# bad_style.net
KiCad netlist of a schematic drawn in EAGLE
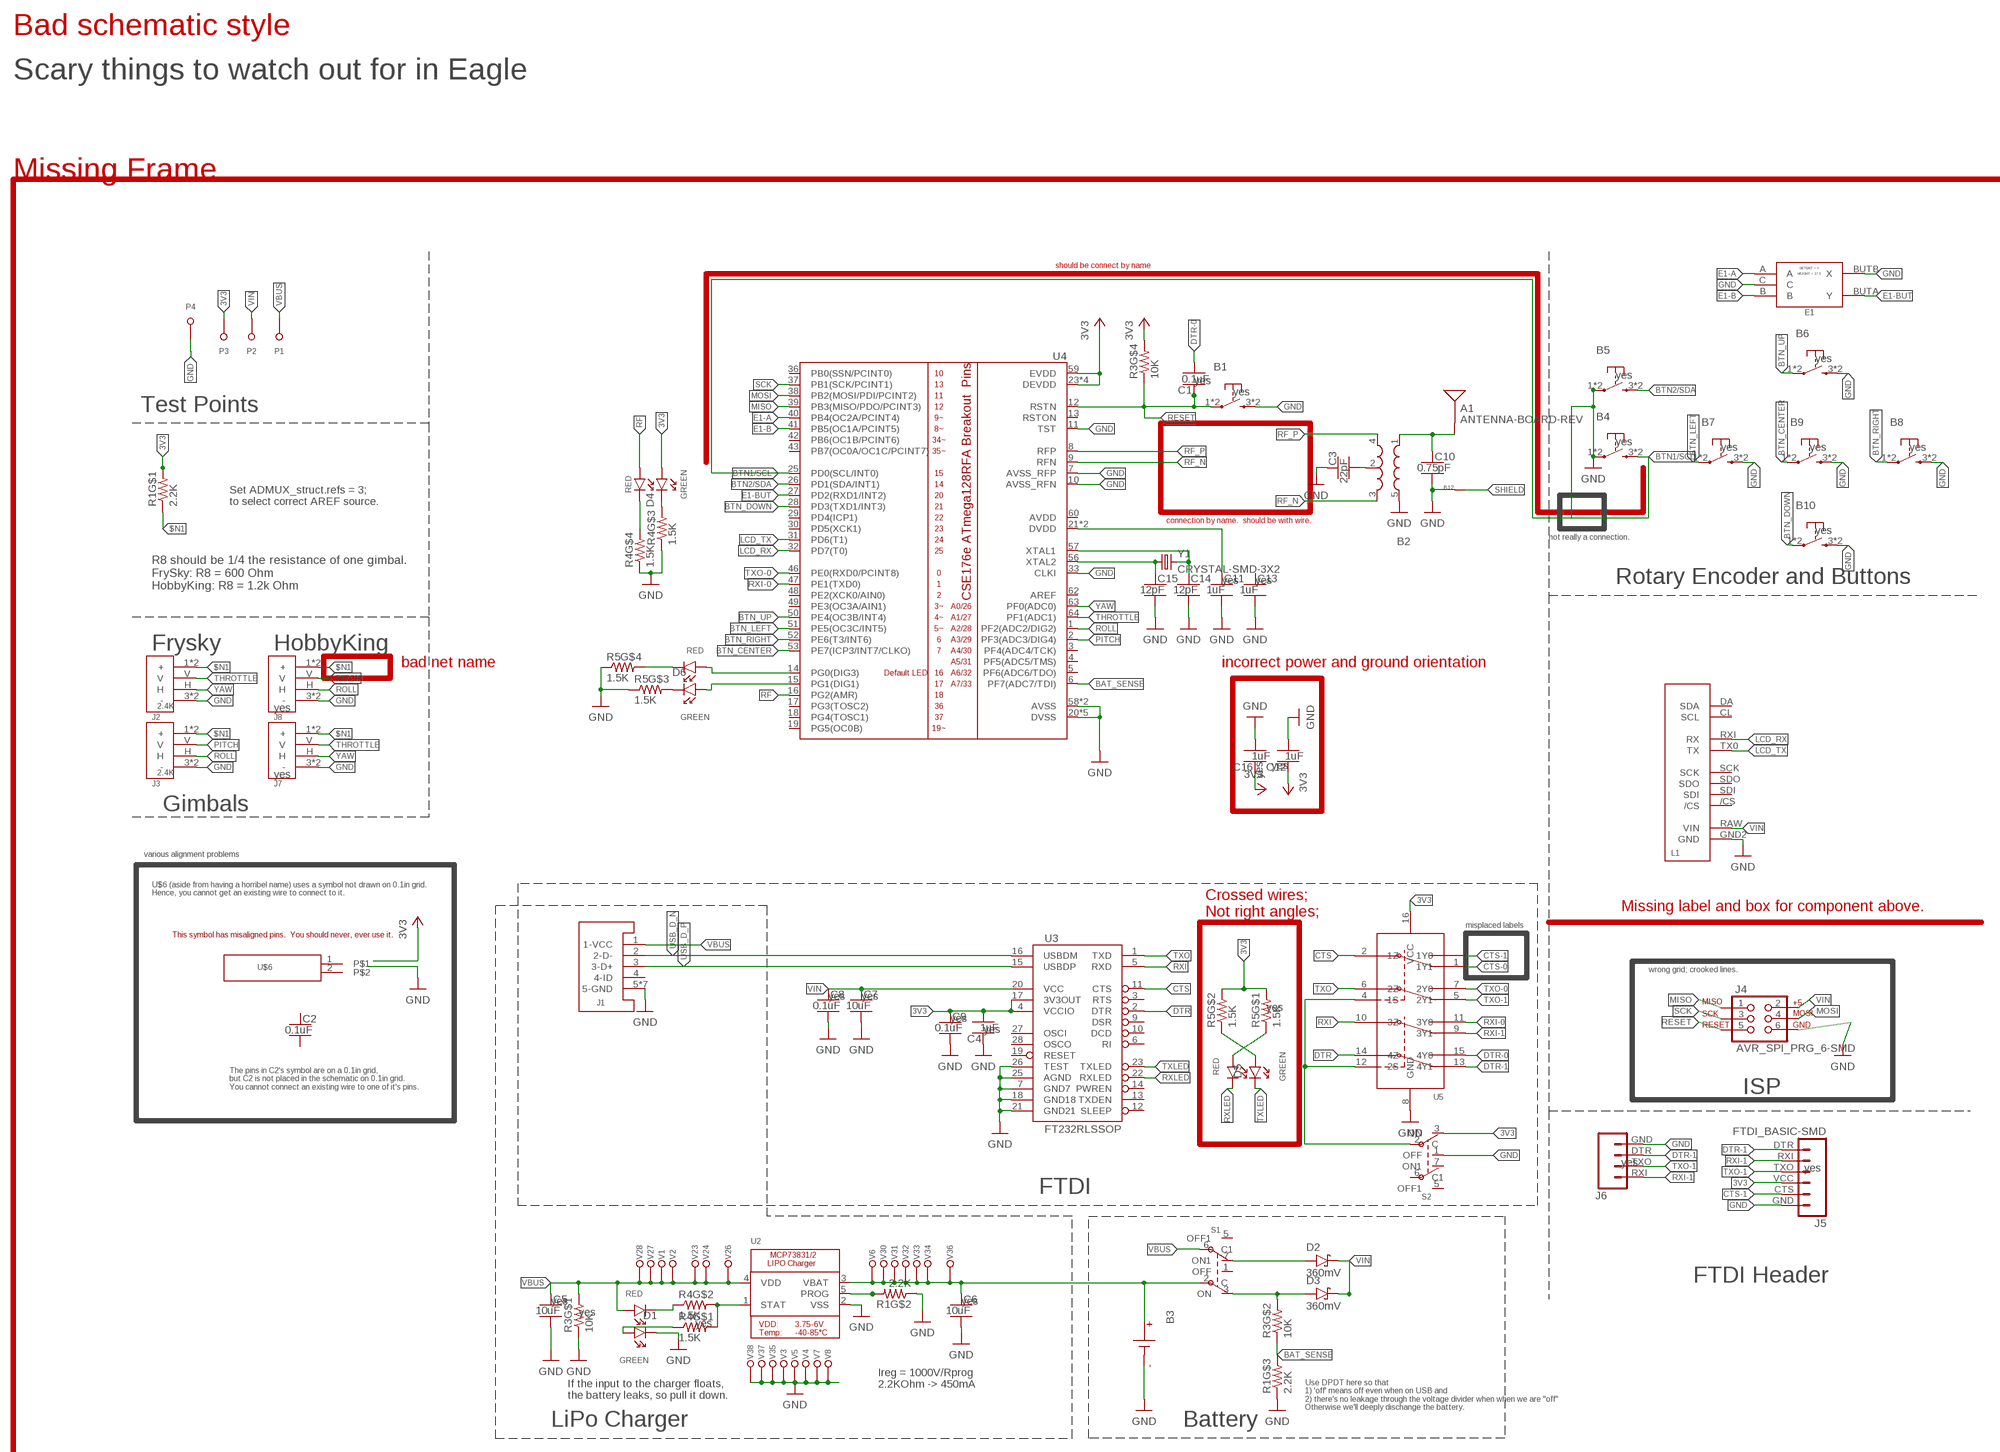
[diagram p0: schematic, sheet 1]

(export (version "E")
  (design (tool "Eeschema 10.0.6"))
  (components
    (comp (ref "A1")
      (value "ANTENNA-BOARD-REV")
      (footprint "eagle-import:ANT_PCB_2.4GHZ_NRF8001_1.6MM_1OZ_REV")
      (fields (field (name "MFR") "NA") (field (name "CREATOR") "Swanson"))
      (libsource (lib "eagle-import") (part "ANTENNA-BOARD-REV"))
    )
    (comp (ref "B1")
      (value "PUSHBUTTON_-4.5X4.5")
      (footprint "eagle-import:4.5MM_TACTILE_SWITCH_TL3305AF160QG")
      (fields
        (field (name "MFR") "E-Switch")
        (field (name "MPN") "TL3305AF160QG")
        (field (name "SUBSTITUTE_OK") "yes")
        (field (name "CREATOR") "Swanson")
      )
      (libsource (lib "eagle-import") (part "PUSHBUTTON_-4.5X4.5"))
    )
    (comp (ref "B2")
      (value "BALUN0805")
      (footprint "eagle-import:BALUN")
      (fields
        (field (name "MFR") "Wurth Electronics Inc.")
        (field (name "MPN") "748421245")
        (field (name "CREATOR") "Swanson")
        (field (name "REVIEWER") "Swanson")
      )
      (libsource (lib "eagle-import") (part "BALUN0805"))
    )
    (comp (ref "B3")
      (value "BATTERY-SMD")
      (footprint "eagle-import:MOLEX-BATTERY-CONNECTOR-SMD-51005-2P")
      (fields (field (name "MFR") "UNKNOWN") (field (name "CREATOR") "Swanson"))
      (libsource (lib "eagle-import") (part "BATTERY-SMD"))
    )
    (comp (ref "B4")
      (value "PUSHBUTTON_-4.5X4.5")
      (footprint "eagle-import:4.5MM_TACTILE_SWITCH_TL3305AF160QG")
      (fields
        (field (name "MFR") "E-Switch")
        (field (name "MPN") "TL3305AF160QG")
        (field (name "SUBSTITUTE_OK") "yes")
        (field (name "CREATOR") "Swanson")
      )
      (libsource (lib "eagle-import") (part "PUSHBUTTON_-4.5X4.5"))
    )
    (comp (ref "B5")
      (value "PUSHBUTTON_-4.5X4.5")
      (footprint "eagle-import:4.5MM_TACTILE_SWITCH_TL3305AF160QG")
      (fields
        (field (name "MFR") "E-Switch")
        (field (name "MPN") "TL3305AF160QG")
        (field (name "SUBSTITUTE_OK") "yes")
        (field (name "CREATOR") "Swanson")
      )
      (libsource (lib "eagle-import") (part "PUSHBUTTON_-4.5X4.5"))
    )
    (comp (ref "B6")
      (value "PUSHBUTTON_-4.5X4.5")
      (footprint "eagle-import:4.5MM_TACTILE_SWITCH_TL3305AF160QG")
      (fields
        (field (name "MFR") "E-Switch")
        (field (name "MPN") "TL3305AF160QG")
        (field (name "SUBSTITUTE_OK") "yes")
        (field (name "CREATOR") "Swanson")
      )
      (libsource (lib "eagle-import") (part "PUSHBUTTON_-4.5X4.5"))
    )
    (comp (ref "B7")
      (value "PUSHBUTTON_-4.5X4.5")
      (footprint "eagle-import:4.5MM_TACTILE_SWITCH_TL3305AF160QG")
      (fields
        (field (name "MFR") "E-Switch")
        (field (name "MPN") "TL3305AF160QG")
        (field (name "SUBSTITUTE_OK") "yes")
        (field (name "CREATOR") "Swanson")
      )
      (libsource (lib "eagle-import") (part "PUSHBUTTON_-4.5X4.5"))
    )
    (comp (ref "B8")
      (value "PUSHBUTTON_-4.5X4.5")
      (footprint "eagle-import:4.5MM_TACTILE_SWITCH_TL3305AF160QG")
      (fields
        (field (name "MFR") "E-Switch")
        (field (name "MPN") "TL3305AF160QG")
        (field (name "SUBSTITUTE_OK") "yes")
        (field (name "CREATOR") "Swanson")
      )
      (libsource (lib "eagle-import") (part "PUSHBUTTON_-4.5X4.5"))
    )
    (comp (ref "B9")
      (value "PUSHBUTTON_-4.5X4.5")
      (footprint "eagle-import:4.5MM_TACTILE_SWITCH_TL3305AF160QG")
      (fields
        (field (name "MFR") "E-Switch")
        (field (name "MPN") "TL3305AF160QG")
        (field (name "SUBSTITUTE_OK") "yes")
        (field (name "CREATOR") "Swanson")
      )
      (libsource (lib "eagle-import") (part "PUSHBUTTON_-4.5X4.5"))
    )
    (comp (ref "B10")
      (value "PUSHBUTTON_-4.5X4.5")
      (footprint "eagle-import:4.5MM_TACTILE_SWITCH_TL3305AF160QG")
      (fields
        (field (name "MFR") "E-Switch")
        (field (name "MPN") "TL3305AF160QG")
        (field (name "SUBSTITUTE_OK") "yes")
        (field (name "CREATOR") "Swanson")
      )
      (libsource (lib "eagle-import") (part "PUSHBUTTON_-4.5X4.5"))
    )
    (comp (ref "B12")
      (value "NET_BRIDGE")
      (footprint "eagle-import:NET_BRIDGE")
      (fields (field (name "MFR") "None") (field (name "CREATOR") "Michael Gonzalez"))
      (libsource (lib "eagle-import") (part "NET_BRIDGE"))
    )
    (comp (ref "C1")
      (value "0.1uF")
      (footprint "eagle-import:CAPC1608X100")
      (fields
        (field (name "MFR") "KEMET")
        (field (name "MPN") "C0603C104K8RACTU")
        (field (name "SUBSTITUTE_OK") "yes")
        (field (name "CREATOR") "Swanson")
      )
      (libsource (lib "eagle-import") (part "CAPACITOR-NP_SMD-0603_CERAMIC-0.1UF"))
    )
    (comp (ref "C2")
      (value "0.1uF")
      (footprint "eagle-import:CAPC1608X100")
      (fields
        (field (name "MFR") "KEMET")
        (field (name "MPN") "C0603C104K8RACTU")
        (field (name "CREATOR") "Swanson")
      )
      (libsource (lib "eagle-import") (part "CAPACITOR-NP_SMD-0603_CERAMIC-0.1UF"))
    )
    (comp (ref "C3")
      (value "22pF")
      (footprint "eagle-import:CAPC1608X100")
      (fields
        (field (name "MFR") "AVX Corporation")
        (field (name "MPN") "06036A220KAT2A")
        (field (name "CREATOR") "Swanson")
      )
      (libsource (lib "eagle-import") (part "CAPACITOR-NP_SMD-0603_CERAMIC-22PF"))
    )
    (comp (ref "C4")
      (value "1uF")
      (footprint "eagle-import:CAPC1608X100")
      (fields
        (field (name "MFR") "Samsung Electro-Mechanics")
        (field (name "MPN") "CL10A105KP8NNNC")
        (field (name "SUBSTITUTE_OK") "yes")
        (field (name "CREATOR") "Swanson")
      )
      (libsource (lib "eagle-import") (part "CAPACITOR-NP_SMD-0603_CERAMIC-1UF"))
    )
    (comp (ref "C5")
      (value "10uF")
      (footprint "eagle-import:CAPC1608X100")
      (fields
        (field (name "MFR") "Samsung Electro-Mechanics")
        (field (name "MPN") "CL10A106MQ8NNNC")
        (field (name "SUBSTITUTE_OK") "yes")
        (field (name "CREATOR") "Swanson")
      )
      (libsource (lib "eagle-import") (part "CAPACITOR-NP_SMD-0603_CERAMIC-10UF"))
    )
    (comp (ref "C6")
      (value "10uF")
      (footprint "eagle-import:CAPC1608X100")
      (fields
        (field (name "MFR") "Samsung Electro-Mechanics")
        (field (name "MPN") "CL10A106MQ8NNNC")
        (field (name "SUBSTITUTE_OK") "yes")
        (field (name "CREATOR") "Swanson")
      )
      (libsource (lib "eagle-import") (part "CAPACITOR-NP_SMD-0603_CERAMIC-10UF"))
    )
    (comp (ref "C7")
      (value "10uF")
      (footprint "eagle-import:CAPC1608X100")
      (fields
        (field (name "MFR") "Samsung Electro-Mechanics")
        (field (name "MPN") "CL10A106MQ8NNNC")
        (field (name "SUBSTITUTE_OK") "yes")
        (field (name "CREATOR") "Swanson")
      )
      (libsource (lib "eagle-import") (part "CAPACITOR-NP_SMD-0603_CERAMIC-10UF"))
    )
    (comp (ref "C8")
      (value "0.1uF")
      (footprint "eagle-import:CAPC1608X100")
      (fields
        (field (name "MFR") "KEMET")
        (field (name "MPN") "C0603C104K8RACTU")
        (field (name "SUBSTITUTE_OK") "yes")
        (field (name "CREATOR") "Swanson")
      )
      (libsource (lib "eagle-import") (part "CAPACITOR-NP_SMD-0603_CERAMIC-0.1UF"))
    )
    (comp (ref "C9")
      (value "0.1uF")
      (footprint "eagle-import:CAPC1608X100")
      (fields
        (field (name "MFR") "KEMET")
        (field (name "MPN") "C0603C104K8RACTU")
        (field (name "SUBSTITUTE_OK") "yes")
        (field (name "CREATOR") "Swanson")
      )
      (libsource (lib "eagle-import") (part "CAPACITOR-NP_SMD-0603_CERAMIC-0.1UF"))
    )
    (comp (ref "C10")
      (value "0.75pF")
      (footprint "eagle-import:CAPC1608X100")
      (fields
        (field (name "MFR") "Yageo")
        (field (name "MPN") "CC0603BRNPO9BNR75")
        (field (name "CREATOR") "Swanson")
      )
      (libsource (lib "eagle-import") (part "CAPACITOR-NP_SMD-0603_CERAMIC-0.75PF"))
    )
    (comp (ref "C11")
      (value "1uF")
      (footprint "eagle-import:CAPC1608X100")
      (fields
        (field (name "MFR") "Samsung Electro-Mechanics")
        (field (name "MPN") "CL10A105KP8NNNC")
        (field (name "SUBSTITUTE_OK") "yes")
        (field (name "CREATOR") "Swanson")
      )
      (libsource (lib "eagle-import") (part "CAPACITOR-NP_SMD-0603_CERAMIC-1UF"))
    )
    (comp (ref "C12")
      (value "1uF")
      (footprint "eagle-import:CAPC1608X100")
      (fields
        (field (name "MFR") "Samsung Electro-Mechanics")
        (field (name "MPN") "CL10A105KP8NNNC")
        (field (name "SUBSTITUTE_OK") "yes")
        (field (name "CREATOR") "Swanson")
      )
      (libsource (lib "eagle-import") (part "CAPACITOR-NP_SMD-0603_CERAMIC-1UF"))
    )
    (comp (ref "C13")
      (value "1uF")
      (footprint "eagle-import:CAPC1608X100")
      (fields
        (field (name "MFR") "Samsung Electro-Mechanics")
        (field (name "MPN") "CL10A105KP8NNNC")
        (field (name "SUBSTITUTE_OK") "yes")
        (field (name "CREATOR") "Swanson")
      )
      (libsource (lib "eagle-import") (part "CAPACITOR-NP_SMD-0603_CERAMIC-1UF"))
    )
    (comp (ref "C14")
      (value "12pF")
      (footprint "eagle-import:CAPC1608X100")
      (fields
        (field (name "MFR") "Vishay Vitramon")
        (field (name "MPN") "VJ0603A120FXQCW1BC")
        (field (name "CREATOR") "Swanson")
      )
      (libsource (lib "eagle-import") (part "CAPACITOR-NP_SMD-0603_CERAMIC-12PF"))
    )
    (comp (ref "C15")
      (value "12pF")
      (footprint "eagle-import:CAPC1608X100")
      (fields
        (field (name "MFR") "Vishay Vitramon")
        (field (name "MPN") "VJ0603A120FXQCW1BC")
        (field (name "CREATOR") "Swanson")
      )
      (libsource (lib "eagle-import") (part "CAPACITOR-NP_SMD-0603_CERAMIC-12PF"))
    )
    (comp (ref "C16")
      (value "1uF")
      (footprint "eagle-import:CAPC1608X100")
      (fields
        (field (name "MFR") "Samsung Electro-Mechanics")
        (field (name "MPN") "CL10A105KP8NNNC")
        (field (name "SUBSTITUTE_OK") "yes")
        (field (name "CREATOR") "Swanson")
      )
      (libsource (lib "eagle-import") (part "CAPACITOR-NP_SMD-0603_CERAMIC-1UF"))
    )
    (comp (ref "D1")
      (value "LED-2X-GREEN/RED-1.6X1.5MM")
      (footprint "eagle-import:LED-2X-LITE-ON-1.6MMX1.5MM")
      (fields
        (field (name "COLOR2") "GREEN")
        (field (name "COLOR1") "RED")
        (field (name "MFR") "Lite-On Inc.")
        (field (name "MPN") "LTST-C195TGKRKT")
        (field (name "CREATOR") "Swanson")
      )
      (libsource (lib "eagle-import") (part "LED-2X-GREEN/RED-1.6X1.5MM"))
    )
    (comp (ref "D2")
      (value "360mV")
      (footprint "eagle-import:SODFL3516X96")
      (fields
        (field (name "MFR") "Toshiba Semiconductor and Storage")
        (field (name "MPN") "CRS08(TE85L,Q,M)")
        (field (name "CREATOR") "Swanson")
        (field (name "REVIEWER") "Swanson")
      )
      (libsource (lib "eagle-import") (part "DIODE-SCHOTTKY_-SMD-SOD123"))
    )
    (comp (ref "D3")
      (value "360mV")
      (footprint "eagle-import:SODFL3516X96")
      (fields
        (field (name "MFR") "Toshiba Semiconductor and Storage")
        (field (name "MPN") "CRS08(TE85L,Q,M)")
        (field (name "CREATOR") "Swanson")
        (field (name "REVIEWER") "Swanson")
      )
      (libsource (lib "eagle-import") (part "DIODE-SCHOTTKY_-SMD-SOD123"))
    )
    (comp (ref "D4")
      (value "LED-2X-GREEN/RED-1.6X1.5MM")
      (footprint "eagle-import:LED-2X-LITE-ON-1.6MMX1.5MM")
      (fields
        (field (name "COLOR2") "GREEN")
        (field (name "COLOR1") "RED")
        (field (name "MFR") "Lite-On Inc.")
        (field (name "MPN") "LTST-C195TGKRKT")
        (field (name "CREATOR") "Swanson")
      )
      (libsource (lib "eagle-import") (part "LED-2X-GREEN/RED-1.6X1.5MM"))
    )
    (comp (ref "D5")
      (value "LED-2X-GREEN/RED-1.6X1.5MM")
      (footprint "eagle-import:LED-2X-LITE-ON-1.6MMX1.5MM")
      (fields
        (field (name "COLOR2") "GREEN")
        (field (name "COLOR1") "RED")
        (field (name "MFR") "Lite-On Inc.")
        (field (name "MPN") "LTST-C195TGKRKT")
        (field (name "CREATOR") "Swanson")
      )
      (libsource (lib "eagle-import") (part "LED-2X-GREEN/RED-1.6X1.5MM"))
    )
    (comp (ref "D6")
      (value "LED-2X-GREEN/RED-1.6X1.5MM")
      (footprint "eagle-import:LED-2X-LITE-ON-1.6MMX1.5MM")
      (fields
        (field (name "COLOR2") "GREEN")
        (field (name "COLOR1") "RED")
        (field (name "MFR") "Lite-On Inc.")
        (field (name "MPN") "LTST-C195TGKRKT")
        (field (name "CREATOR") "Swanson")
      )
      (libsource (lib "eagle-import") (part "LED-2X-GREEN/RED-1.6X1.5MM"))
    )
    (comp (ref "E1")
      (value "ROTARY-ENCODER-W/BUTTON-BOURNS-PEC12R-4217F")
      (footprint "eagle-import:BOURNS-PEC12R")
      (fields (field (name "DETENT") "Y") (field (name "HEIGHT") "17.5") (field (name "CREATOR") "Swanson"))
      (libsource (lib "eagle-import") (part "ROTARY-ENCODER-W/BUTTON-BOURNS-PEC12R-4217F"))
    )
    (comp (ref "J1")
      (value "USB-MICROA-AMPHENOL-10118192-0001LF")
      (footprint "eagle-import:USB-MICROA-10118192-0001LF")
      (fields
        (field (name "MFR") "Amphenol ICC (FCI)")
        (field (name "MPN") "10118192-0001LF")
        (field (name "CREATOR") "Swanson")
      )
      (libsource (lib "eagle-import") (part "USB-MICROA-AMPHENOL-10118192-0001LF"))
    )
    (comp (ref "J2")
      (value "2.4K")
      (footprint "eagle-import:JST-13-PTH")
      (fields
        (field (name "MFR") "TE Connectivity AMP Connectors")
        (field (name "MPN") "1-1735446-2")
        (field (name "CREATOR") "Swanson")
      )
      (libsource (lib "eagle-import") (part "FRSKY-GIMBAL-FRYSKY"))
    )
    (comp (ref "J3")
      (value "2.4K")
      (footprint "eagle-import:JST-13-PTH")
      (fields
        (field (name "MFR") "TE Connectivity AMP Connectors")
        (field (name "MPN") "1-1735446-2")
        (field (name "SPICEPREFIX") "E")
        (field (name "CREATOR") "Swanson")
      )
      (libsource (lib "eagle-import") (part "FRSKY-GIMBAL-FRYSKY"))
    )
    (comp (ref "J4")
      (value "AVR_SPI_PRG_6-SMD")
      (footprint "eagle-import:2X3-SMD")
      (fields
        (field (name "MFR") "Amphenol ICC (FCI)")
        (field (name "MPN") "95278-101A06LF")
        (field (name "CREATOR") "Swanson")
      )
      (libsource (lib "eagle-import") (part "AVR_SPI_PRG_6-SMD"))
    )
    (comp (ref "J5")
      (value "FTDI_BASIC-SMD")
      (footprint "eagle-import:FTDI-BASIC-SMD")
      (fields
        (field (name "MFR") "Harwin Inc.")
        (field (name "MPN") "M20-8890645")
        (field (name "SUBSTITUTE_OK") "yes")
        (field (name "CREATOR") "Swanson")
      )
      (libsource (lib "eagle-import") (part "FTDI_BASIC-SMD"))
    )
    (comp (ref "J6")
      (value "FTDI-4PIN-RIGHT-ANGLE-SMD")
      (footprint "eagle-import:HEADER-2X2-0.1IN-MALE-RIGHT-ANGLE-SMD")
      (fields
        (field (name "MFR") "Samtec Inc.")
        (field (name "MPN") "TSM-102-01-L-DH")
        (field (name "SUBSTITUTE_OK") "yes")
        (field (name "CREATOR") "Swanson")
      )
      (libsource (lib "eagle-import") (part "FTDI-4PIN-RIGHT-ANGLE-SMD"))
    )
    (comp (ref "J7")
      (value "FRSKY-GIMBAL-2X-SERVO-SMD")
      (footprint "eagle-import:2X-SERVO-SMD")
      (fields
        (field (name "MFR") "Harwin Inc.")
        (field (name "MPN") "M20-8890645")
        (field (name "SUBSTITUTE_OK") "yes")
        (field (name "CREATOR") "Swanson")
      )
      (libsource (lib "eagle-import") (part "FRSKY-GIMBAL-2X-SERVO-SMD"))
    )
    (comp (ref "J8")
      (value "FRSKY-GIMBAL-2X-SERVO-SMD")
      (footprint "eagle-import:2X-SERVO-SMD")
      (fields
        (field (name "MFR") "Harwin Inc.")
        (field (name "MPN") "M20-8890645")
        (field (name "SUBSTITUTE_OK") "yes")
        (field (name "CREATOR") "Swanson")
      )
      (libsource (lib "eagle-import") (part "FRSKY-GIMBAL-2X-SERVO-SMD"))
    )
    (comp (ref "L1")
      (value "SPARKFUN_SERLCD_SERIAL_REDUCED-SMD")
      (footprint "eagle-import:SPARKFUN_SERLCD_16X2_REDUCED_SMD")
      (fields
        (field (name "MFR") "Sullins Connector Solutions")
        (field (name "MPN") "NPPC101KFXC-RC")
        (field (name "CREATOR") "Swanson")
      )
      (libsource (lib "eagle-import") (part "SPARKFUN_SERLCD_SERIAL_REDUCED-SMD"))
    )
    (comp (ref "P1")
      (value "TEST-POINT")
      (footprint "eagle-import:TEST-POINT-KEYSTONE-5000")
      (fields
        (field (name "MFR") "Keystone Electronics")
        (field (name "MPN") "5001")
        (field (name "CREATOR") "Swanson")
      )
      (libsource (lib "eagle-import") (part "TEST-POINT"))
    )
    (comp (ref "P2")
      (value "TEST-POINT")
      (footprint "eagle-import:TEST-POINT-KEYSTONE-5000")
      (fields
        (field (name "MFR") "Keystone Electronics")
        (field (name "MPN") "5001")
        (field (name "CREATOR") "Swanson")
      )
      (libsource (lib "eagle-import") (part "TEST-POINT"))
    )
    (comp (ref "P3")
      (value "TEST-POINT")
      (footprint "eagle-import:TEST-POINT-KEYSTONE-5000")
      (fields
        (field (name "MFR") "Keystone Electronics")
        (field (name "MPN") "5001")
        (field (name "CREATOR") "Swanson")
      )
      (libsource (lib "eagle-import") (part "TEST-POINT"))
    )
    (comp (ref "P4")
      (value "TEST-POINT")
      (footprint "eagle-import:TEST-POINT-KEYSTONE-5000")
      (fields
        (field (name "MFR") "Keystone Electronics")
        (field (name "MPN") "5001")
        (field (name "CREATOR") "Swanson")
      )
      (libsource (lib "eagle-import") (part "TEST-POINT"))
    )
    (comp (ref "R1")
      (value "2.2K")
      (footprint "eagle-import:RESCAXS50P200X100X45-8")
      (fields
        (field (name "MFR") "Panasonic Electronic Components")
        (field (name "MPN") "EXB-N8V221JX")
        (field (name "SUBSTITUTE_OK") "yes")
        (field (name "CREATOR") "Swanson")
      )
      (libsource (lib "eagle-import") (part "RESISTOR-PACK-4X-2.2K"))
    )
    (comp (ref "R3")
      (value "10K")
      (footprint "eagle-import:RESCAXS50P200X100X45-8")
      (fields
        (field (name "MFR") "Panasonic Electronic Components")
        (field (name "MPN") "EXB-N8V103JX")
        (field (name "SUBSTITUTE_OK") "yes")
        (field (name "CREATOR") "Swanson")
      )
      (libsource (lib "eagle-import") (part "RESISTOR-PACK-4X-10K"))
    )
    (comp (ref "R4")
      (value "1.5K")
      (footprint "eagle-import:RESCAXS50P200X100X45-8")
      (fields
        (field (name "MFR") "Panasonic Electronic Components")
        (field (name "MPN") "EXB-N8V152JX")
        (field (name "SUBSTITUTE_OK") "yes")
        (field (name "CREATOR") "Swanson")
      )
      (libsource (lib "eagle-import") (part "RESISTOR-PACK-4X-1.5K"))
    )
    (comp (ref "R5")
      (value "1.5K")
      (footprint "eagle-import:RESCAXS50P200X100X45-8")
      (fields
        (field (name "MFR") "Panasonic Electronic Components")
        (field (name "MPN") "EXB-N8V152JX")
        (field (name "SUBSTITUTE_OK") "yes")
        (field (name "CREATOR") "Swanson")
      )
      (libsource (lib "eagle-import") (part "RESISTOR-PACK-4X-1.5K"))
    )
    (comp (ref "S1")
      (value "SWITCH-DPDT-300MA-6V-SMD")
      (footprint "eagle-import:JS202011JCQN")
      (fields
        (field (name "MFR") "C&K")
        (field (name "MPN") "JS202011JCQN")
        (field (name "CREATOR") "Swanson")
      )
      (libsource (lib "eagle-import") (part "SWITCH-DPDT-300MA-6V-SMD"))
    )
    (comp (ref "S2")
      (value "SWITCH-DPDT-300MA-6V-SMD")
      (footprint "eagle-import:JS202011JCQN")
      (fields
        (field (name "MFR") "C&K")
        (field (name "MPN") "JS202011JCQN")
        (field (name "CREATOR") "Swanson")
      )
      (libsource (lib "eagle-import") (part "SWITCH-DPDT-300MA-6V-SMD"))
    )
    (comp (ref "U$6")
      (value "DONT_USE")
      (footprint "eagle-import:SCREW-TERMINAL-1X2-2.54MM")
      (libsource (lib "eagle-import") (part "DONT_USE"))
    )
    (comp (ref "U2")
      (value "MCP73831T-2ACI/OT")
      (footprint "eagle-import:SOT23-5")
      (fields (field (name "MFR") "Microchip Technology") (field (name "CREATOR") "Adafruit"))
      (libsource (lib "eagle-import") (part "MCP73831/2"))
    )
    (comp (ref "U3")
      (value "FT232RLSSOP")
      (footprint "eagle-import:SSOP28DB")
      (fields
        (field (name "MFR") "FTDI")
        (field (name "MPN") "FT232RL-REEL")
        (field (name "CREATOR") "Swanson")
      )
      (libsource (lib "eagle-import") (part "FT232RLSSOP"))
    )
    (comp (ref "U4")
      (value "ATMEGA128RFA1")
      (footprint "eagle-import:QFN-64")
      (fields
        (field (name "MFR") "Microchip Technology")
        (field (name "MPN") "ATMEGA128RFA1-ZU")
        (field (name "CREATOR") "Swanson")
        (field (name "REVIEWER") "Swanson")
      )
      (libsource (lib "eagle-import") (part "ATMEGA128RFA1"))
    )
    (comp (ref "U5")
      (value "DPDT-X2")
      (footprint "eagle-import:SOP65P640X110-16")
      (fields
        (field (name "MFR") "NXP USA Inc.")
        (field (name "MPN") "NX3L2467PW,118")
        (field (name "CREATOR") "Swanson")
      )
      (libsource (lib "eagle-import") (part "DPDT-X2"))
    )
    (comp (ref "V1")
      (value "LOCKED-VIA-0.2")
      (footprint "eagle-import:VIA-0.2MM")
      (fields (field (name "MFR") "NA") (field (name "CREATOR") "Swanson"))
      (libsource (lib "eagle-import") (part "LOCKED-VIA-0.2"))
    )
    (comp (ref "V2")
      (value "LOCKED-VIA-0.2")
      (footprint "eagle-import:VIA-0.2MM")
      (fields (field (name "MFR") "NA") (field (name "CREATOR") "Swanson"))
      (libsource (lib "eagle-import") (part "LOCKED-VIA-0.2"))
    )
    (comp (ref "V3")
      (value "LOCKED-VIA-0.2")
      (footprint "eagle-import:VIA-0.2MM")
      (fields (field (name "MFR") "NA") (field (name "CREATOR") "Swanson"))
      (libsource (lib "eagle-import") (part "LOCKED-VIA-0.2"))
    )
    (comp (ref "V4")
      (value "LOCKED-VIA-0.2")
      (footprint "eagle-import:VIA-0.2MM")
      (fields (field (name "MFR") "NA") (field (name "CREATOR") "Swanson"))
      (libsource (lib "eagle-import") (part "LOCKED-VIA-0.2"))
    )
    (comp (ref "V5")
      (value "LOCKED-VIA-0.2")
      (footprint "eagle-import:VIA-0.2MM")
      (fields (field (name "MFR") "NA") (field (name "CREATOR") "Swanson"))
      (libsource (lib "eagle-import") (part "LOCKED-VIA-0.2"))
    )
    (comp (ref "V6")
      (value "LOCKED-VIA-0.2")
      (footprint "eagle-import:VIA-0.2MM")
      (fields (field (name "MFR") "NA") (field (name "CREATOR") "Swanson"))
      (libsource (lib "eagle-import") (part "LOCKED-VIA-0.2"))
    )
    (comp (ref "V7")
      (value "LOCKED-VIA-0.2")
      (footprint "eagle-import:VIA-0.2MM")
      (fields (field (name "MFR") "NA") (field (name "CREATOR") "Swanson"))
      (libsource (lib "eagle-import") (part "LOCKED-VIA-0.2"))
    )
    (comp (ref "V8")
      (value "LOCKED-VIA-0.2")
      (footprint "eagle-import:VIA-0.2MM")
      (fields (field (name "MFR") "NA") (field (name "CREATOR") "Swanson"))
      (libsource (lib "eagle-import") (part "LOCKED-VIA-0.2"))
    )
    (comp (ref "V23")
      (value "LOCKED-VIA-0.2")
      (footprint "eagle-import:VIA-0.2MM")
      (fields (field (name "MFR") "NA") (field (name "CREATOR") "Swanson"))
      (libsource (lib "eagle-import") (part "LOCKED-VIA-0.2"))
    )
    (comp (ref "V24")
      (value "LOCKED-VIA-0.2")
      (footprint "eagle-import:VIA-0.2MM")
      (fields (field (name "MFR") "NA") (field (name "CREATOR") "Swanson"))
      (libsource (lib "eagle-import") (part "LOCKED-VIA-0.2"))
    )
    (comp (ref "V26")
      (value "LOCKED-VIA-0.2")
      (footprint "eagle-import:VIA-0.2MM")
      (fields (field (name "MFR") "NA") (field (name "CREATOR") "Swanson"))
      (libsource (lib "eagle-import") (part "LOCKED-VIA-0.2"))
    )
    (comp (ref "V27")
      (value "LOCKED-VIA-0.2")
      (footprint "eagle-import:VIA-0.2MM")
      (fields (field (name "MFR") "NA") (field (name "CREATOR") "Swanson"))
      (libsource (lib "eagle-import") (part "LOCKED-VIA-0.2"))
    )
    (comp (ref "V28")
      (value "LOCKED-VIA-0.2")
      (footprint "eagle-import:VIA-0.2MM")
      (fields (field (name "MFR") "NA") (field (name "CREATOR") "Swanson"))
      (libsource (lib "eagle-import") (part "LOCKED-VIA-0.2"))
    )
    (comp (ref "V30")
      (value "LOCKED-VIA-0.2")
      (footprint "eagle-import:VIA-0.2MM")
      (fields (field (name "MFR") "NA") (field (name "CREATOR") "Swanson"))
      (libsource (lib "eagle-import") (part "LOCKED-VIA-0.2"))
    )
    (comp (ref "V31")
      (value "LOCKED-VIA-0.2")
      (footprint "eagle-import:VIA-0.2MM")
      (fields (field (name "MFR") "NA") (field (name "CREATOR") "Swanson"))
      (libsource (lib "eagle-import") (part "LOCKED-VIA-0.2"))
    )
    (comp (ref "V32")
      (value "LOCKED-VIA-0.2")
      (footprint "eagle-import:VIA-0.2MM")
      (fields (field (name "MFR") "NA") (field (name "CREATOR") "Swanson"))
      (libsource (lib "eagle-import") (part "LOCKED-VIA-0.2"))
    )
    (comp (ref "V33")
      (value "LOCKED-VIA-0.2")
      (footprint "eagle-import:VIA-0.2MM")
      (fields (field (name "MFR") "NA") (field (name "CREATOR") "Swanson"))
      (libsource (lib "eagle-import") (part "LOCKED-VIA-0.2"))
    )
    (comp (ref "V34")
      (value "LOCKED-VIA-0.2")
      (footprint "eagle-import:VIA-0.2MM")
      (fields (field (name "MFR") "NA") (field (name "CREATOR") "Swanson"))
      (libsource (lib "eagle-import") (part "LOCKED-VIA-0.2"))
    )
    (comp (ref "V35")
      (value "LOCKED-VIA-0.2")
      (footprint "eagle-import:VIA-0.2MM")
      (fields (field (name "MFR") "NA") (field (name "CREATOR") "Swanson"))
      (libsource (lib "eagle-import") (part "LOCKED-VIA-0.2"))
    )
    (comp (ref "V36")
      (value "LOCKED-VIA-0.2")
      (footprint "eagle-import:VIA-0.2MM")
      (fields (field (name "MFR") "NA") (field (name "CREATOR") "Swanson"))
      (libsource (lib "eagle-import") (part "LOCKED-VIA-0.2"))
    )
    (comp (ref "V37")
      (value "LOCKED-VIA-0.2")
      (footprint "eagle-import:VIA-0.2MM")
      (fields (field (name "MFR") "NA") (field (name "CREATOR") "Swanson"))
      (libsource (lib "eagle-import") (part "LOCKED-VIA-0.2"))
    )
    (comp (ref "V38")
      (value "LOCKED-VIA-0.2")
      (footprint "eagle-import:VIA-0.2MM")
      (fields (field (name "MFR") "NA") (field (name "CREATOR") "Swanson"))
      (libsource (lib "eagle-import") (part "LOCKED-VIA-0.2"))
    )
    (comp (ref "Y1")
      (value "CRYSTAL-SMD-3X2")
      (footprint "eagle-import:OSCCC320X250X85")
      (fields
        (field (name "MFR") "Abracon LLC")
        (field (name "MPN") "ABM8-16.000MHZ-B2-T")
        (field (name "CREATOR") "Swanson")
      )
      (libsource (lib "eagle-import") (part "CRYSTAL-SMD-3X2"))
    )
  )
  (nets
    (net (code "1") (name "$N1") (class "Default")
      (node (ref "J2") (pin "1") (pinfunction "+_1") (pintype "bidirectional"))
      (node (ref "J2") (pin "4") (pinfunction "+_4") (pintype "bidirectional"))
      (node (ref "J3") (pin "1") (pinfunction "+_1") (pintype "bidirectional"))
      (node (ref "J3") (pin "4") (pinfunction "+_4") (pintype "bidirectional"))
      (node (ref "J7") (pin "1") (pinfunction "+_1") (pintype "bidirectional"))
      (node (ref "J7") (pin "4") (pinfunction "+_4") (pintype "bidirectional"))
      (node (ref "J8") (pin "1") (pinfunction "+_1") (pintype "bidirectional"))
      (node (ref "J8") (pin "4") (pinfunction "+_4") (pintype "bidirectional"))
      (node (ref "R1") (pin "4") (pinfunction "1_4") (pintype "passive"))
    )
    (net (code "2") (name "3V3") (class "Default")
      (node (ref "C12") (pin "1") (pinfunction "1_1") (pintype "passive"))
      (node (ref "C16") (pin "1") (pinfunction "1_1") (pintype "passive"))
      (node (ref "C4") (pin "2") (pinfunction "2_2") (pintype "passive"))
      (node (ref "C9") (pin "1") (pinfunction "1_1") (pintype "passive"))
      (node (ref "D4") (pin "A1") (pinfunction "A1_A1") (pintype "passive"))
      (node (ref "J5") (pin "VCC") (pinfunction "4_VCC") (pintype "passive"))
      (node (ref "P3") (pin "T") (pinfunction "T_T") (pintype "bidirectional"))
      (node (ref "R1") (pin "5") (pinfunction "2_5") (pintype "passive"))
      (node (ref "R3") (pin "8") (pinfunction "2_8") (pintype "passive"))
      (node (ref "R5") (pin "5") (pinfunction "2_5") (pintype "passive"))
      (node (ref "R5") (pin "6") (pinfunction "2_6") (pintype "passive"))
      (node (ref "S2") (pin "3") (pinfunction "ON_3") (pintype "bidirectional"))
      (node (ref "U3") (pin "17") (pinfunction "3V3OUT_17") (pintype "output"))
      (node (ref "U3") (pin "4") (pinfunction "VCCIO_4") (pintype "power_in"))
      (node (ref "U4") (pin "23") (pinfunction "DEVDD_23") (pintype "bidirectional"))
      (node (ref "U4") (pin "34") (pinfunction "DEVDD_34") (pintype "bidirectional"))
      (node (ref "U4") (pin "44") (pinfunction "DEVDD_44") (pintype "bidirectional"))
      (node (ref "U4") (pin "54") (pinfunction "DEVDD_54") (pintype "bidirectional"))
      (node (ref "U4") (pin "59") (pinfunction "EVDD_59") (pintype "bidirectional"))
      (node (ref "U5") (pin "16") (pinfunction "VCC_16") (pintype "bidirectional"))
    )
    (net (code "3") (name "BAT_SENSE") (class "Default")
      (node (ref "R1") (pin "7") (pinfunction "2_7") (pintype "passive"))
      (node (ref "R3") (pin "3") (pinfunction "1_3") (pintype "passive"))
      (node (ref "U4") (pin "6") (pinfunction "PF7(ADC7/TDI)_6") (pintype "bidirectional"))
    )
    (net (code "4") (name "BTN1{slash}SCL") (class "Default")
      (node (ref "B4") (pin "3") (pinfunction "2_3") (pintype "passive"))
      (node (ref "B4") (pin "4") (pinfunction "2_4") (pintype "passive"))
      (node (ref "U4") (pin "25") (pinfunction "PD0(SCL/INT0)_25") (pintype "bidirectional"))
    )
    (net (code "5") (name "BTN2{slash}SDA") (class "Default")
      (node (ref "B5") (pin "3") (pinfunction "2_3") (pintype "passive"))
      (node (ref "B5") (pin "4") (pinfunction "2_4") (pintype "passive"))
      (node (ref "U4") (pin "26") (pinfunction "PD1(SDA/INT1)_26") (pintype "bidirectional"))
    )
    (net (code "6") (name "BTN_CENTER") (class "Default")
      (node (ref "B9") (pin "1") (pinfunction "1_1") (pintype "passive"))
      (node (ref "B9") (pin "2") (pinfunction "1_2") (pintype "passive"))
      (node (ref "U4") (pin "53") (pinfunction "PE7(ICP3/INT7/CLKO)_53") (pintype "bidirectional"))
    )
    (net (code "7") (name "BTN_DOWN") (class "Default")
      (node (ref "B10") (pin "1") (pinfunction "1_1") (pintype "passive"))
      (node (ref "B10") (pin "2") (pinfunction "1_2") (pintype "passive"))
      (node (ref "U4") (pin "28") (pinfunction "PD3(TXD1/INT3)_28") (pintype "bidirectional"))
    )
    (net (code "8") (name "BTN_LEFT") (class "Default")
      (node (ref "B7") (pin "1") (pinfunction "1_1") (pintype "passive"))
      (node (ref "B7") (pin "2") (pinfunction "1_2") (pintype "passive"))
      (node (ref "U4") (pin "51") (pinfunction "PE5(OC3C/INT5)_51") (pintype "bidirectional"))
    )
    (net (code "9") (name "BTN_RIGHT") (class "Default")
      (node (ref "B8") (pin "1") (pinfunction "1_1") (pintype "passive"))
      (node (ref "B8") (pin "2") (pinfunction "1_2") (pintype "passive"))
      (node (ref "U4") (pin "52") (pinfunction "PE6(T3/INT6)_52") (pintype "bidirectional"))
    )
    (net (code "10") (name "BTN_UP") (class "Default")
      (node (ref "B6") (pin "1") (pinfunction "1_1") (pintype "passive"))
      (node (ref "B6") (pin "2") (pinfunction "1_2") (pintype "passive"))
      (node (ref "U4") (pin "50") (pinfunction "PE4(OC3B/INT4)_50") (pintype "bidirectional"))
    )
    (net (code "11") (name "CTS") (class "Default")
      (node (ref "U3") (pin "11") (pinfunction "CTS_11") (pintype "input"))
      (node (ref "U5") (pin "2") (pinfunction "1Z_2") (pintype "bidirectional"))
    )
    (net (code "12") (name "CTS-0") (class "Default")
      (node (ref "U5") (pin "3") (pinfunction "1Y0_3") (pintype "bidirectional"))
    )
    (net (code "13") (name "CTS-1") (class "Default")
      (node (ref "J5") (pin "CTS") (pinfunction "5_CTS") (pintype "passive"))
      (node (ref "U5") (pin "1") (pinfunction "1Y1_1") (pintype "bidirectional"))
    )
    (net (code "14") (name "DTR") (class "Default")
      (node (ref "U3") (pin "2") (pinfunction "DTR_2") (pintype "output"))
      (node (ref "U5") (pin "14") (pinfunction "4Z_14") (pintype "bidirectional"))
    )
    (net (code "15") (name "DTR-0") (class "Default")
      (node (ref "C1") (pin "2") (pinfunction "2_2") (pintype "passive"))
      (node (ref "U5") (pin "15") (pinfunction "4Y0_15") (pintype "bidirectional"))
    )
    (net (code "16") (name "DTR-1") (class "Default")
      (node (ref "J5") (pin "DTR") (pinfunction "1_DTR") (pintype "passive"))
      (node (ref "J6") (pin "DTR") (pinfunction "3_DTR") (pintype "bidirectional"))
      (node (ref "U5") (pin "13") (pinfunction "4Y1_13") (pintype "bidirectional"))
    )
    (net (code "17") (name "E1-A") (class "Default")
      (node (ref "E1") (pin "A") (pinfunction "A_A") (pintype "bidirectional"))
      (node (ref "U4") (pin "40") (pinfunction "PB4(OC2A/PCINT4)_40") (pintype "bidirectional"))
    )
    (net (code "18") (name "E1-B") (class "Default")
      (node (ref "E1") (pin "B") (pinfunction "B_B") (pintype "bidirectional"))
      (node (ref "U4") (pin "41") (pinfunction "PB5(OC1A/PCINT5)_41") (pintype "bidirectional"))
    )
    (net (code "19") (name "E1-BUT") (class "Default")
      (node (ref "E1") (pin "BUTA") (pinfunction "Y_BUTA") (pintype "bidirectional"))
      (node (ref "U4") (pin "27") (pinfunction "PD2(RXD1/INT2)_27") (pintype "bidirectional"))
    )
    (net (code "20") (name "GND") (class "Default")
      (node (ref "B1") (pin "3") (pinfunction "2_3") (pintype "passive"))
      (node (ref "B1") (pin "4") (pinfunction "2_4") (pintype "passive"))
      (node (ref "B10") (pin "3") (pinfunction "2_3") (pintype "passive"))
      (node (ref "B10") (pin "4") (pinfunction "2_4") (pintype "passive"))
      (node (ref "B12") (pin "P1") (pinfunction "P1_P1") (pintype "bidirectional"))
      (node (ref "B2") (pin "5") (pinfunction "GND_5") (pintype "bidirectional"))
      (node (ref "B3") (pin "G") (pinfunction "N_G") (pintype "bidirectional"))
      (node (ref "B3") (pin "G2") (pinfunction "N_G2") (pintype "bidirectional"))
      (node (ref "B3") (pin "G3") (pinfunction "N_G3") (pintype "bidirectional"))
      (node (ref "B4") (pin "1") (pinfunction "1_1") (pintype "passive"))
      (node (ref "B4") (pin "2") (pinfunction "1_2") (pintype "passive"))
      (node (ref "B5") (pin "1") (pinfunction "1_1") (pintype "passive"))
      (node (ref "B5") (pin "2") (pinfunction "1_2") (pintype "passive"))
      (node (ref "B6") (pin "3") (pinfunction "2_3") (pintype "passive"))
      (node (ref "B6") (pin "4") (pinfunction "2_4") (pintype "passive"))
      (node (ref "B7") (pin "3") (pinfunction "2_3") (pintype "passive"))
      (node (ref "B7") (pin "4") (pinfunction "2_4") (pintype "passive"))
      (node (ref "B8") (pin "3") (pinfunction "2_3") (pintype "passive"))
      (node (ref "B8") (pin "4") (pinfunction "2_4") (pintype "passive"))
      (node (ref "B9") (pin "3") (pinfunction "2_3") (pintype "passive"))
      (node (ref "B9") (pin "4") (pinfunction "2_4") (pintype "passive"))
      (node (ref "C10") (pin "2") (pinfunction "2_2") (pintype "passive"))
      (node (ref "C11") (pin "2") (pinfunction "2_2") (pintype "passive"))
      (node (ref "C12") (pin "2") (pinfunction "2_2") (pintype "passive"))
      (node (ref "C13") (pin "2") (pinfunction "2_2") (pintype "passive"))
      (node (ref "C14") (pin "2") (pinfunction "2_2") (pintype "passive"))
      (node (ref "C15") (pin "2") (pinfunction "2_2") (pintype "passive"))
      (node (ref "C16") (pin "2") (pinfunction "2_2") (pintype "passive"))
      (node (ref "C3") (pin "1") (pinfunction "1_1") (pintype "passive"))
      (node (ref "C4") (pin "1") (pinfunction "1_1") (pintype "passive"))
      (node (ref "C5") (pin "2") (pinfunction "2_2") (pintype "passive"))
      (node (ref "C6") (pin "2") (pinfunction "2_2") (pintype "passive"))
      (node (ref "C7") (pin "2") (pinfunction "2_2") (pintype "passive"))
      (node (ref "C8") (pin "2") (pinfunction "2_2") (pintype "passive"))
      (node (ref "C9") (pin "2") (pinfunction "2_2") (pintype "passive"))
      (node (ref "D1") (pin "C1") (pinfunction "C1_C1") (pintype "passive"))
      (node (ref "E1") (pin "BUTB") (pinfunction "X_BUTB") (pintype "bidirectional"))
      (node (ref "E1") (pin "C") (pinfunction "C_C") (pintype "bidirectional"))
      (node (ref "J1") (pin "10") (pinfunction "5-GND_10") (pintype "bidirectional"))
      (node (ref "J1") (pin "11") (pinfunction "5-GND_11") (pintype "bidirectional"))
      (node (ref "J1") (pin "5") (pinfunction "5-GND_5") (pintype "bidirectional"))
      (node (ref "J1") (pin "6") (pinfunction "5-GND_6") (pintype "bidirectional"))
      (node (ref "J1") (pin "7") (pinfunction "5-GND_7") (pintype "bidirectional"))
      (node (ref "J1") (pin "8") (pinfunction "5-GND_8") (pintype "bidirectional"))
      (node (ref "J1") (pin "9") (pinfunction "5-GND_9") (pintype "bidirectional"))
      (node (ref "J2") (pin "3") (pinfunction "-_3") (pintype "bidirectional"))
      (node (ref "J2") (pin "6") (pinfunction "-_6") (pintype "bidirectional"))
      (node (ref "J3") (pin "3") (pinfunction "-_3") (pintype "bidirectional"))
      (node (ref "J3") (pin "6") (pinfunction "-_6") (pintype "bidirectional"))
      (node (ref "J4") (pin "6") (pinfunction "6_6") (pintype "passive"))
      (node (ref "J5") (pin "GND") (pinfunction "6_GND") (pintype "passive"))
      (node (ref "J6") (pin "GND") (pinfunction "4_GND") (pintype "bidirectional"))
      (node (ref "J7") (pin "3") (pinfunction "-_3") (pintype "bidirectional"))
      (node (ref "J7") (pin "6") (pinfunction "-_6") (pintype "bidirectional"))
      (node (ref "J8") (pin "3") (pinfunction "-_3") (pintype "bidirectional"))
      (node (ref "J8") (pin "6") (pinfunction "-_6") (pintype "bidirectional"))
      (node (ref "L1") (pin "GND2") (pinfunction "GND_GND2") (pintype "bidirectional"))
      (node (ref "P4") (pin "T") (pinfunction "T_T") (pintype "bidirectional"))
      (node (ref "R1") (pin "2") (pinfunction "1_2") (pintype "passive"))
      (node (ref "R1") (pin "3") (pinfunction "1_3") (pintype "passive"))
      (node (ref "R3") (pin "4") (pinfunction "1_4") (pintype "passive"))
      (node (ref "R4") (pin "1") (pinfunction "1_1") (pintype "passive"))
      (node (ref "R4") (pin "2") (pinfunction "1_2") (pintype "passive"))
      (node (ref "R5") (pin "1") (pinfunction "1_1") (pintype "passive"))
      (node (ref "R5") (pin "2") (pinfunction "1_2") (pintype "passive"))
      (node (ref "S2") (pin "1") (pinfunction "OFF_1") (pintype "bidirectional"))
      (node (ref "U2") (pin "2") (pinfunction "VSS_2") (pintype "power_in"))
      (node (ref "U3") (pin "18") (pinfunction "GND18_18") (pintype "power_in"))
      (node (ref "U3") (pin "21") (pinfunction "GND21_21") (pintype "power_in"))
      (node (ref "U3") (pin "25") (pinfunction "AGND_25") (pintype "power_in"))
      (node (ref "U3") (pin "26") (pinfunction "TEST_26") (pintype "input"))
      (node (ref "U3") (pin "7") (pinfunction "GND7_7") (pintype "power_in"))
      (node (ref "U4") (pin "10") (pinfunction "AVSS_RFN_10") (pintype "bidirectional"))
      (node (ref "U4") (pin "11") (pinfunction "TST_11") (pintype "bidirectional"))
      (node (ref "U4") (pin "20") (pinfunction "DVSS_20") (pintype "bidirectional"))
      (node (ref "U4") (pin "24") (pinfunction "DVSS_24") (pintype "bidirectional"))
      (node (ref "U4") (pin "33") (pinfunction "CLKI_33") (pintype "bidirectional"))
      (node (ref "U4") (pin "35") (pinfunction "DVSS_35") (pintype "bidirectional"))
      (node (ref "U4") (pin "45") (pinfunction "DVSS_45") (pintype "bidirectional"))
      (node (ref "U4") (pin "55") (pinfunction "DVSS_55") (pintype "bidirectional"))
      (node (ref "U4") (pin "58") (pinfunction "AVSS_58") (pintype "bidirectional"))
      (node (ref "U4") (pin "61") (pinfunction "AVSS_61") (pintype "bidirectional"))
      (node (ref "U4") (pin "7") (pinfunction "AVSS_RFP_7") (pintype "bidirectional"))
      (node (ref "U5") (pin "8") (pinfunction "GND_8") (pintype "bidirectional"))
      (node (ref "V3") (pin "P1") (pinfunction "N_P1") (pintype "bidirectional"))
      (node (ref "V35") (pin "P1") (pinfunction "N_P1") (pintype "bidirectional"))
      (node (ref "V37") (pin "P1") (pinfunction "N_P1") (pintype "bidirectional"))
      (node (ref "V38") (pin "P1") (pinfunction "N_P1") (pintype "bidirectional"))
      (node (ref "V4") (pin "P1") (pinfunction "N_P1") (pintype "bidirectional"))
      (node (ref "V5") (pin "P1") (pinfunction "N_P1") (pintype "bidirectional"))
      (node (ref "V7") (pin "P1") (pinfunction "N_P1") (pintype "bidirectional"))
      (node (ref "V8") (pin "P1") (pinfunction "N_P1") (pintype "bidirectional"))
    )
    (net (code "21") (name "LCD_RX") (class "Default")
      (node (ref "L1") (pin "RXI") (pinfunction "RX_RXI") (pintype "bidirectional"))
      (node (ref "U4") (pin "32") (pinfunction "PD7(T0)_32") (pintype "bidirectional"))
    )
    (net (code "22") (name "LCD_TX") (class "Default")
      (node (ref "L1") (pin "TX0") (pinfunction "TX_TX0") (pintype "bidirectional"))
      (node (ref "U4") (pin "31") (pinfunction "PD6(T1)_31") (pintype "bidirectional"))
    )
    (net (code "23") (name "MISO") (class "Default")
      (node (ref "J4") (pin "1") (pinfunction "1_1") (pintype "passive"))
      (node (ref "U4") (pin "39") (pinfunction "PB3(MISO/PDO/PCINT3)_39") (pintype "bidirectional"))
    )
    (net (code "24") (name "MOSI") (class "Default")
      (node (ref "J4") (pin "4") (pinfunction "4_4") (pintype "passive"))
      (node (ref "U4") (pin "38") (pinfunction "PB2(MOSI/PDI/PCINT2)_38") (pintype "bidirectional"))
    )
    (net (code "25") (name "Net-(A1-SIGNAL)") (class "Default")
      (node (ref "A1") (pin "FEED") (pinfunction "SIGNAL_FEED") (pintype "bidirectional"))
      (node (ref "B2") (pin "1") (pinfunction "IN_1") (pintype "bidirectional"))
      (node (ref "C10") (pin "1") (pinfunction "1_1") (pintype "passive"))
    )
    (net (code "26") (name "Net-(B2-GND-Pad2)") (class "Default")
      (node (ref "B2") (pin "2") (pinfunction "GND_2") (pintype "bidirectional"))
      (node (ref "C3") (pin "2") (pinfunction "2_2") (pintype "passive"))
    )
    (net (code "27") (name "Net-(C11-Pad1)") (class "Default")
      (node (ref "C11") (pin "1") (pinfunction "1_1") (pintype "passive"))
      (node (ref "U4") (pin "21") (pinfunction "DVDD_21") (pintype "bidirectional"))
      (node (ref "U4") (pin "22") (pinfunction "DVDD_22") (pintype "bidirectional"))
    )
    (net (code "28") (name "Net-(D2-A)") (class "Default")
      (node (ref "D2") (pin "2") (pinfunction "A_2") (pintype "passive"))
      (node (ref "S1") (pin "7") (pinfunction "ON1_7") (pintype "bidirectional"))
    )
    (net (code "29") (name "Net-(D3-A)") (class "Default")
      (node (ref "D3") (pin "2") (pinfunction "A_2") (pintype "passive"))
      (node (ref "R3") (pin "6") (pinfunction "2_6") (pintype "passive"))
      (node (ref "S1") (pin "3") (pinfunction "ON_3") (pintype "bidirectional"))
    )
    (net (code "30") (name "Net-(R1B-2)") (class "Default")
      (node (ref "R1") (pin "6") (pinfunction "2_6") (pintype "passive"))
      (node (ref "U2") (pin "5") (pinfunction "PROG_5") (pintype "input"))
    )
    (net (code "31") (name "Net-(R4A-1)") (class "Default")
      (node (ref "D1") (pin "A1") (pinfunction "A1_A1") (pintype "passive"))
      (node (ref "R4") (pin "4") (pinfunction "1_4") (pintype "passive"))
    )
    (net (code "32") (name "Net-(R4A-2)") (class "Default")
      (node (ref "R4") (pin "5") (pinfunction "2_5") (pintype "passive"))
      (node (ref "R4") (pin "6") (pinfunction "2_6") (pintype "passive"))
      (node (ref "U2") (pin "1") (pinfunction "STAT_1") (pintype "output"))
    )
    (net (code "33") (name "Net-(R4B-1)") (class "Default")
      (node (ref "D1") (pin "C2") (pinfunction "C2_C2") (pintype "passive"))
      (node (ref "R4") (pin "3") (pinfunction "1_3") (pintype "passive"))
    )
    (net (code "34") (name "Net-(R4C-2)") (class "Default")
      (node (ref "D4") (pin "C1") (pinfunction "C1_C1") (pintype "passive"))
      (node (ref "R4") (pin "7") (pinfunction "2_7") (pintype "passive"))
    )
    (net (code "35") (name "Net-(R4D-2)") (class "Default")
      (node (ref "D4") (pin "C2") (pinfunction "C2_C2") (pintype "passive"))
      (node (ref "R4") (pin "8") (pinfunction "2_8") (pintype "passive"))
    )
    (net (code "36") (name "Net-(R5A-1)") (class "Default")
      (node (ref "D5") (pin "A2") (pinfunction "A2_A2") (pintype "passive"))
      (node (ref "R5") (pin "4") (pinfunction "1_4") (pintype "passive"))
    )
    (net (code "37") (name "Net-(R5B-1)") (class "Default")
      (node (ref "D5") (pin "A1") (pinfunction "A1_A1") (pintype "passive"))
      (node (ref "R5") (pin "3") (pinfunction "1_3") (pintype "passive"))
    )
    (net (code "38") (name "Net-(R5C-2)") (class "Default")
      (node (ref "D6") (pin "C1") (pinfunction "C1_C1") (pintype "passive"))
      (node (ref "R5") (pin "7") (pinfunction "2_7") (pintype "passive"))
    )
    (net (code "39") (name "Net-(R5D-2)") (class "Default")
      (node (ref "D6") (pin "C2") (pinfunction "C2_C2") (pintype "passive"))
      (node (ref "R5") (pin "8") (pinfunction "2_8") (pintype "passive"))
    )
    (net (code "40") (name "Net-(S1-C)") (class "Default")
      (node (ref "B3") (pin "P") (pinfunction "P_P") (pintype "bidirectional"))
      (node (ref "C6") (pin "1") (pinfunction "1_1") (pintype "passive"))
      (node (ref "S1") (pin "2") (pinfunction "C_2") (pintype "bidirectional"))
      (node (ref "U2") (pin "3") (pinfunction "VBAT_3") (pintype "power_in"))
      (node (ref "V30") (pin "P1") (pinfunction "N_P1") (pintype "bidirectional"))
      (node (ref "V31") (pin "P1") (pinfunction "N_P1") (pintype "bidirectional"))
      (node (ref "V32") (pin "P1") (pinfunction "N_P1") (pintype "bidirectional"))
      (node (ref "V33") (pin "P1") (pinfunction "N_P1") (pintype "bidirectional"))
      (node (ref "V34") (pin "P1") (pinfunction "N_P1") (pintype "bidirectional"))
      (node (ref "V36") (pin "P1") (pinfunction "N_P1") (pintype "bidirectional"))
      (node (ref "V6") (pin "P1") (pinfunction "N_P1") (pintype "bidirectional"))
    )
    (net (code "41") (name "Net-(S2-C)") (class "Default")
      (node (ref "S2") (pin "2") (pinfunction "C_2") (pintype "bidirectional"))
      (node (ref "U5") (pin "12") (pinfunction "2S_12") (pintype "bidirectional"))
      (node (ref "U5") (pin "4") (pinfunction "1S_4") (pintype "bidirectional"))
    )
    (net (code "42") (name "Net-(U4-PG0(DIG3))") (class "Default")
      (node (ref "D6") (pin "A2") (pinfunction "A2_A2") (pintype "passive"))
      (node (ref "U4") (pin "14") (pinfunction "PG0(DIG3)_14") (pintype "bidirectional"))
    )
    (net (code "43") (name "Net-(U4-PG1(DIG1))") (class "Default")
      (node (ref "D6") (pin "A1") (pinfunction "A1_A1") (pintype "passive"))
      (node (ref "U4") (pin "15") (pinfunction "PG1(DIG1)_15") (pintype "bidirectional"))
    )
    (net (code "44") (name "Net-(U4-XTAL1)") (class "Default")
      (node (ref "C14") (pin "1") (pinfunction "1_1") (pintype "passive"))
      (node (ref "U4") (pin "57") (pinfunction "XTAL1_57") (pintype "bidirectional"))
      (node (ref "Y1") (pin "3") (pinfunction "2_3") (pintype "passive"))
    )
    (net (code "45") (name "Net-(U4-XTAL2)") (class "Default")
      (node (ref "C15") (pin "1") (pinfunction "1_1") (pintype "passive"))
      (node (ref "U4") (pin "56") (pinfunction "XTAL2_56") (pintype "bidirectional"))
      (node (ref "Y1") (pin "1") (pinfunction "1_1") (pintype "passive"))
    )
    (net (code "46") (name "PITCH") (class "Default")
      (node (ref "J3") (pin "V") (pinfunction "V_V") (pintype "bidirectional"))
      (node (ref "J8") (pin "V") (pinfunction "V_V") (pintype "bidirectional"))
      (node (ref "U4") (pin "2") (pinfunction "PF3(ADC3/DIG4)_2") (pintype "bidirectional"))
    )
    (net (code "47") (name "RESET") (class "Default")
      (node (ref "B1") (pin "1") (pinfunction "1_1") (pintype "passive"))
      (node (ref "B1") (pin "2") (pinfunction "1_2") (pintype "passive"))
      (node (ref "C1") (pin "1") (pinfunction "1_1") (pintype "passive"))
      (node (ref "J4") (pin "5") (pinfunction "5_5") (pintype "passive"))
      (node (ref "R3") (pin "1") (pinfunction "1_1") (pintype "passive"))
      (node (ref "U4") (pin "12") (pinfunction "RSTN_12") (pintype "bidirectional"))
    )
    (net (code "48") (name "RF") (class "Default")
      (node (ref "D4") (pin "A2") (pinfunction "A2_A2") (pintype "passive"))
      (node (ref "U4") (pin "16") (pinfunction "PG2(AMR)_16") (pintype "bidirectional"))
    )
    (net (code "49") (name "RF_N") (class "Default")
      (node (ref "B2") (pin "3") (pinfunction "OUT2_3") (pintype "bidirectional"))
      (node (ref "U4") (pin "9") (pinfunction "RFN_9") (pintype "bidirectional"))
    )
    (net (code "50") (name "RF_P") (class "Default")
      (node (ref "B2") (pin "4") (pinfunction "OUT1_4") (pintype "bidirectional"))
      (node (ref "U4") (pin "8") (pinfunction "RFP_8") (pintype "bidirectional"))
    )
    (net (code "51") (name "ROLL") (class "Default")
      (node (ref "J3") (pin "H") (pinfunction "H_H") (pintype "bidirectional"))
      (node (ref "J8") (pin "H") (pinfunction "H_H") (pintype "bidirectional"))
      (node (ref "U4") (pin "1") (pinfunction "PF2(ADC2/DIG2)_1") (pintype "bidirectional"))
    )
    (net (code "52") (name "RXI") (class "Default")
      (node (ref "U3") (pin "5") (pinfunction "RXD_5") (pintype "input"))
      (node (ref "U5") (pin "10") (pinfunction "3Z_10") (pintype "bidirectional"))
    )
    (net (code "53") (name "RXI-0") (class "Default")
      (node (ref "U4") (pin "47") (pinfunction "PE1(TXD0)_47") (pintype "bidirectional"))
      (node (ref "U5") (pin "11") (pinfunction "3Y0_11") (pintype "bidirectional"))
    )
    (net (code "54") (name "RXI-1") (class "Default")
      (node (ref "J5") (pin "RXI") (pinfunction "2_RXI") (pintype "passive"))
      (node (ref "J6") (pin "RXI") (pinfunction "1_RXI") (pintype "bidirectional"))
      (node (ref "U5") (pin "9") (pinfunction "3Y1_9") (pintype "bidirectional"))
    )
    (net (code "55") (name "RXLED") (class "Default")
      (node (ref "D5") (pin "C2") (pinfunction "C2_C2") (pintype "passive"))
      (node (ref "U3") (pin "22") (pinfunction "RXLED_22") (pintype "input"))
    )
    (net (code "56") (name "SCK") (class "Default")
      (node (ref "J4") (pin "3") (pinfunction "3_3") (pintype "passive"))
      (node (ref "U4") (pin "37") (pinfunction "PB1(SCK/PCINT1)_37") (pintype "bidirectional"))
    )
    (net (code "57") (name "SHIELD") (class "Default")
      (node (ref "B12") (pin "P2") (pinfunction "P2_P2") (pintype "bidirectional"))
    )
    (net (code "58") (name "THROTTLE") (class "Default")
      (node (ref "J2") (pin "V") (pinfunction "V_V") (pintype "bidirectional"))
      (node (ref "J7") (pin "V") (pinfunction "V_V") (pintype "bidirectional"))
      (node (ref "U4") (pin "64") (pinfunction "PF1(ADC1)_64") (pintype "bidirectional"))
    )
    (net (code "59") (name "TXLED") (class "Default")
      (node (ref "D5") (pin "C1") (pinfunction "C1_C1") (pintype "passive"))
      (node (ref "U3") (pin "23") (pinfunction "TXLED_23") (pintype "input"))
    )
    (net (code "60") (name "TXO") (class "Default")
      (node (ref "U3") (pin "1") (pinfunction "TXD_1") (pintype "output"))
      (node (ref "U5") (pin "6") (pinfunction "2Z_6") (pintype "bidirectional"))
    )
    (net (code "61") (name "TXO-0") (class "Default")
      (node (ref "U4") (pin "46") (pinfunction "PE0(RXD0/PCINT8)_46") (pintype "bidirectional"))
      (node (ref "U5") (pin "7") (pinfunction "2Y0_7") (pintype "bidirectional"))
    )
    (net (code "62") (name "TXO-1") (class "Default")
      (node (ref "J5") (pin "TXO") (pinfunction "3_TXO") (pintype "passive"))
      (node (ref "J6") (pin "TXO") (pinfunction "2_TXO") (pintype "bidirectional"))
      (node (ref "U5") (pin "5") (pinfunction "2Y1_5") (pintype "bidirectional"))
    )
    (net (code "63") (name "USB_D_N") (class "Default")
      (node (ref "J1") (pin "2") (pinfunction "2-D-_2") (pintype "bidirectional"))
      (node (ref "U3") (pin "16") (pinfunction "USBDM_16") (pintype "bidirectional"))
    )
    (net (code "64") (name "USB_D_P") (class "Default")
      (node (ref "J1") (pin "3") (pinfunction "3-D+_3") (pintype "bidirectional"))
      (node (ref "U3") (pin "15") (pinfunction "USBDP_15") (pintype "bidirectional"))
    )
    (net (code "65") (name "VBUS") (class "Default")
      (node (ref "C5") (pin "1") (pinfunction "1_1") (pintype "passive"))
      (node (ref "D1") (pin "A2") (pinfunction "A2_A2") (pintype "passive"))
      (node (ref "J1") (pin "1") (pinfunction "1-VCC_1") (pintype "bidirectional"))
      (node (ref "P1") (pin "T") (pinfunction "T_T") (pintype "bidirectional"))
      (node (ref "R3") (pin "5") (pinfunction "2_5") (pintype "passive"))
      (node (ref "S1") (pin "6") (pinfunction "C1_6") (pintype "bidirectional"))
      (node (ref "U2") (pin "4") (pinfunction "VDD_4") (pintype "power_in"))
      (node (ref "V1") (pin "P1") (pinfunction "N_P1") (pintype "bidirectional"))
      (node (ref "V2") (pin "P1") (pinfunction "N_P1") (pintype "bidirectional"))
      (node (ref "V23") (pin "P1") (pinfunction "N_P1") (pintype "bidirectional"))
      (node (ref "V24") (pin "P1") (pinfunction "N_P1") (pintype "bidirectional"))
      (node (ref "V26") (pin "P1") (pinfunction "N_P1") (pintype "bidirectional"))
      (node (ref "V27") (pin "P1") (pinfunction "N_P1") (pintype "bidirectional"))
      (node (ref "V28") (pin "P1") (pinfunction "N_P1") (pintype "bidirectional"))
    )
    (net (code "66") (name "VIN") (class "Default")
      (node (ref "C7") (pin "1") (pinfunction "1_1") (pintype "passive"))
      (node (ref "C8") (pin "1") (pinfunction "1_1") (pintype "passive"))
      (node (ref "D2") (pin "1") (pinfunction "C_1") (pintype "passive"))
      (node (ref "D3") (pin "1") (pinfunction "C_1") (pintype "passive"))
      (node (ref "J4") (pin "2") (pinfunction "2_2") (pintype "passive"))
      (node (ref "L1") (pin "RAW") (pinfunction "VIN_RAW") (pintype "bidirectional"))
      (node (ref "P2") (pin "T") (pinfunction "T_T") (pintype "bidirectional"))
      (node (ref "U3") (pin "20") (pinfunction "VCC_20") (pintype "power_in"))
    )
    (net (code "67") (name "YAW") (class "Default")
      (node (ref "J2") (pin "H") (pinfunction "H_H") (pintype "bidirectional"))
      (node (ref "J7") (pin "H") (pinfunction "H_H") (pintype "bidirectional"))
      (node (ref "U4") (pin "63") (pinfunction "PF0(ADC0)_63") (pintype "bidirectional"))
    )
    (net (code "68") (name "unconnected-(C2-Pad1)") (class "Default")
      (node (ref "C2") (pin "1") (pinfunction "1_1") (pintype "passive"))
    )
    (net (code "69") (name "unconnected-(C2-Pad2)") (class "Default")
      (node (ref "C2") (pin "2") (pinfunction "2_2") (pintype "passive"))
    )
    (net (code "70") (name "unconnected-(C13-Pad1)") (class "Default")
      (node (ref "C13") (pin "1") (pinfunction "1_1") (pintype "passive"))
    )
    (net (code "71") (name "unconnected-(J1-4-ID-Pad4)") (class "Default")
      (node (ref "J1") (pin "4") (pinfunction "4-ID_4") (pintype "bidirectional"))
    )
    (net (code "72") (name "unconnected-(L1-PadSCK)") (class "Default")
      (node (ref "L1") (pin "SCK") (pinfunction "SCK_SCK") (pintype "bidirectional"))
    )
    (net (code "73") (name "unconnected-(L1-PadSDI)") (class "Default")
      (node (ref "L1") (pin "SDI") (pinfunction "SDI_SDI") (pintype "bidirectional"))
    )
    (net (code "74") (name "unconnected-(L1-PadSDO)") (class "Default")
      (node (ref "L1") (pin "SDO") (pinfunction "SDO_SDO") (pintype "bidirectional"))
    )
    (net (code "75") (name "unconnected-(L1-Pad{slash}CS)") (class "Default")
      (node (ref "L1") (pin "/CS") (pinfunction "/CS_/CS") (pintype "bidirectional"))
    )
    (net (code "76") (name "unconnected-(L1-SCL-PadCL)") (class "Default")
      (node (ref "L1") (pin "CL") (pinfunction "SCL_CL") (pintype "bidirectional"))
    )
    (net (code "77") (name "unconnected-(L1-SDA-PadDA)") (class "Default")
      (node (ref "L1") (pin "DA") (pinfunction "SDA_DA") (pintype "bidirectional"))
    )
    (net (code "78") (name "unconnected-(S1-OFF-Pad1)") (class "Default")
      (node (ref "S1") (pin "1") (pinfunction "OFF_1") (pintype "bidirectional"))
    )
    (net (code "79") (name "unconnected-(S1-OFF1-Pad5)") (class "Default")
      (node (ref "S1") (pin "5") (pinfunction "OFF1_5") (pintype "bidirectional"))
    )
    (net (code "80") (name "unconnected-(S2-C1-Pad6)") (class "Default")
      (node (ref "S2") (pin "6") (pinfunction "C1_6") (pintype "bidirectional"))
    )
    (net (code "81") (name "unconnected-(S2-OFF1-Pad5)") (class "Default")
      (node (ref "S2") (pin "5") (pinfunction "OFF1_5") (pintype "bidirectional"))
    )
    (net (code "82") (name "unconnected-(S2-ON1-Pad7)") (class "Default")
      (node (ref "S2") (pin "7") (pinfunction "ON1_7") (pintype "bidirectional"))
    )
    (net (code "83") (name "unconnected-(U$6-P$1-Pad1)") (class "Default")
      (node (ref "U$6") (pin "1") (pinfunction "P$1_1") (pintype "bidirectional"))
    )
    (net (code "84") (name "unconnected-(U$6-P$2-Pad2)") (class "Default")
      (node (ref "U$6") (pin "2") (pinfunction "P$2_2") (pintype "bidirectional"))
    )
    (net (code "85") (name "unconnected-(U3-DCD-Pad10)") (class "Default")
      (node (ref "U3") (pin "10") (pinfunction "DCD_10") (pintype "input"))
    )
    (net (code "86") (name "unconnected-(U3-DSR-Pad9)") (class "Default")
      (node (ref "U3") (pin "9") (pinfunction "DSR_9") (pintype "input"))
    )
    (net (code "87") (name "unconnected-(U3-OSCI-Pad27)") (class "Default")
      (node (ref "U3") (pin "27") (pinfunction "OSCI_27") (pintype "input"))
    )
    (net (code "88") (name "unconnected-(U3-OSCO-Pad28)") (class "Default")
      (node (ref "U3") (pin "28") (pinfunction "OSCO_28") (pintype "output"))
    )
    (net (code "89") (name "unconnected-(U3-PWREN-Pad14)") (class "Default")
      (node (ref "U3") (pin "14") (pinfunction "PWREN_14") (pintype "input"))
    )
    (net (code "90") (name "unconnected-(U3-RESET-Pad19)") (class "Default")
      (node (ref "U3") (pin "19") (pinfunction "RESET_19") (pintype "input"))
    )
    (net (code "91") (name "unconnected-(U3-RI-Pad6)") (class "Default")
      (node (ref "U3") (pin "6") (pinfunction "RI_6") (pintype "input"))
    )
    (net (code "92") (name "unconnected-(U3-RTS-Pad3)") (class "Default")
      (node (ref "U3") (pin "3") (pinfunction "RTS_3") (pintype "output"))
    )
    (net (code "93") (name "unconnected-(U3-SLEEP-Pad12)") (class "Default")
      (node (ref "U3") (pin "12") (pinfunction "SLEEP_12") (pintype "input"))
    )
    (net (code "94") (name "unconnected-(U3-TXDEN-Pad13)") (class "Default")
      (node (ref "U3") (pin "13") (pinfunction "TXDEN_13") (pintype "input"))
    )
    (net (code "95") (name "unconnected-(U4-AREF-Pad62)") (class "Default")
      (node (ref "U4") (pin "62") (pinfunction "AREF_62") (pintype "bidirectional"))
    )
    (net (code "96") (name "unconnected-(U4-AVDD-Pad60)") (class "Default")
      (node (ref "U4") (pin "60") (pinfunction "AVDD_60") (pintype "bidirectional"))
    )
    (net (code "97") (name "unconnected-(U4-PB0(SSN{slash}PCINT0)-Pad36)") (class "Default")
      (node (ref "U4") (pin "36") (pinfunction "PB0(SSN/PCINT0)_36") (pintype "bidirectional"))
    )
    (net (code "98") (name "unconnected-(U4-PB6(OC1B{slash}PCINT6)-Pad42)") (class "Default")
      (node (ref "U4") (pin "42") (pinfunction "PB6(OC1B/PCINT6)_42") (pintype "bidirectional"))
    )
    (net (code "99") (name "unconnected-(U4-PB7(OC0A{slash}OC1C{slash}PCINT7)-Pad43)") (class "Default")
      (node (ref "U4") (pin "43") (pinfunction "PB7(OC0A/OC1C/PCINT7)_43") (pintype "bidirectional"))
    )
    (net (code "100") (name "unconnected-(U4-PD4(ICP1)-Pad29)") (class "Default")
      (node (ref "U4") (pin "29") (pinfunction "PD4(ICP1)_29") (pintype "bidirectional"))
    )
    (net (code "101") (name "unconnected-(U4-PD5(XCK1)-Pad30)") (class "Default")
      (node (ref "U4") (pin "30") (pinfunction "PD5(XCK1)_30") (pintype "bidirectional"))
    )
    (net (code "102") (name "unconnected-(U4-PE2(XCK0{slash}AIN0)-Pad48)") (class "Default")
      (node (ref "U4") (pin "48") (pinfunction "PE2(XCK0/AIN0)_48") (pintype "bidirectional"))
    )
    (net (code "103") (name "unconnected-(U4-PE3(OC3A{slash}AIN1)-Pad49)") (class "Default")
      (node (ref "U4") (pin "49") (pinfunction "PE3(OC3A/AIN1)_49") (pintype "bidirectional"))
    )
    (net (code "104") (name "unconnected-(U4-PF4(ADC4{slash}TCK)-Pad3)") (class "Default")
      (node (ref "U4") (pin "3") (pinfunction "PF4(ADC4/TCK)_3") (pintype "bidirectional"))
    )
    (net (code "105") (name "unconnected-(U4-PF5(ADC5{slash}TMS)-Pad4)") (class "Default")
      (node (ref "U4") (pin "4") (pinfunction "PF5(ADC5/TMS)_4") (pintype "bidirectional"))
    )
    (net (code "106") (name "unconnected-(U4-PF6(ADC6{slash}TDO)-Pad5)") (class "Default")
      (node (ref "U4") (pin "5") (pinfunction "PF6(ADC6/TDO)_5") (pintype "bidirectional"))
    )
    (net (code "107") (name "unconnected-(U4-PG3(TOSC2)-Pad17)") (class "Default")
      (node (ref "U4") (pin "17") (pinfunction "PG3(TOSC2)_17") (pintype "bidirectional"))
    )
    (net (code "108") (name "unconnected-(U4-PG4(TOSC1)-Pad18)") (class "Default")
      (node (ref "U4") (pin "18") (pinfunction "PG4(TOSC1)_18") (pintype "bidirectional"))
    )
    (net (code "109") (name "unconnected-(U4-PG5(OC0B)-Pad19)") (class "Default")
      (node (ref "U4") (pin "19") (pinfunction "PG5(OC0B)_19") (pintype "bidirectional"))
    )
    (net (code "110") (name "unconnected-(U4-RSTON-Pad13)") (class "Default")
      (node (ref "U4") (pin "13") (pinfunction "RSTON_13") (pintype "bidirectional"))
    )
  )
)
